# usb2serial.net
KiCad netlist of a schematic drawn in Altium Designer
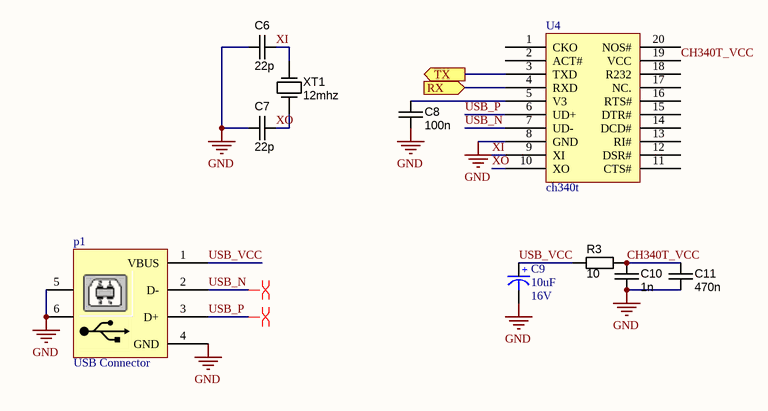
[diagram p0: usb2serial.SchDoc]

(export (version "E")
  (design (tool "Eeschema 10.0.6"))
  (components
    (comp (ref "C6")
      (value "22p")
      (footprint "CAPC1608X90N")
      (description "Capacitor 0603")
      (fields (field (name "TOLERANCE") "±10%"))
      (libsource (lib "PBL - Capacitors") (part "CAPC_1n_0603_X7R_100V_10%"))
    )
    (comp (ref "C7")
      (value "22p")
      (footprint "CAPC1608X90N")
      (description "Capacitor 0603")
      (fields (field (name "TOLERANCE") "±10%"))
      (libsource (lib "PBL - Capacitors") (part "CAPC_1n_0603_X7R_100V_10%"))
    )
    (comp (ref "C8")
      (value "100n")
      (footprint "CAPC1608X90N")
      (description "Capacitor 0603")
      (fields (field (name "TOLERANCE") "±10%"))
      (libsource (lib "PBL - Capacitors") (part "CAPC_1n_0603_X7R_100V_10%"))
    )
    (comp (ref "C9")
      (value "10uF")
      (footprint "cap 01")
      (description "Polar Capacitor")
      (fields (field (name "VOLTAGE") "16V") (field (name "DESIGNER") "Saeid Jorablo"))
      (libsource (lib "My Library") (part "Cap-Polar"))
    )
    (comp (ref "C10")
      (value "1n")
      (footprint "CAPC1608X90N")
      (description "Capacitor 0603")
      (fields (field (name "TOLERANCE") "±10%"))
      (libsource (lib "PBL - Capacitors") (part "CAPC_1n_0603_X7R_100V_10%"))
    )
    (comp (ref "C11")
      (value "470n")
      (footprint "CAPC1608X90N")
      (description "Capacitor 0603")
      (fields (field (name "TOLERANCE") "±10%"))
      (libsource (lib "PBL - Capacitors") (part "CAPC_1n_0603_X7R_100V_10%"))
    )
    (comp (ref "p1")
      (value "USB Connector")
      (footprint "USB2.5-2V4")
      (description "USB Connector-B Type")
      (fields (field (name "DESIGNER") "Eng. Saeid Jorablo"))
      (libsource (lib "My Library") (part "USB"))
    )
    (comp (ref "R3")
      (value "10")
      (footprint "RESC1608X55N")
      (description "Resistor 0603")
      (fields (field (name "TOLERANCE") "±5%"))
      (libsource (lib "PBL - Resistors") (part "RES_2K2_0603_5%"))
    )
    (comp (ref "U4")
      (value "ch340t")
      (footprint "LSSOP65P640X145-20N")
      (libsource (lib "sorour") (part "ch340t"))
    )
    (comp (ref "XT1")
      (value "12mhz")
      (footprint "CRYSTAL_HC49-US-SM")
      (description "Crystal")
      (libsource (lib "PBL - Resonators") (part "Crystal_6MHz_HC49/US"))
    )
  )
  (nets
    (net (code "1") (name "/CH340T_VCC") (class "Default")
      (node (ref "C10") (pin "2") (pintype "passive"))
      (node (ref "C11") (pin "2") (pintype "passive"))
      (node (ref "R3") (pin "2") (pinfunction "2_2") (pintype "passive"))
      (node (ref "U4") (pin "19") (pinfunction "VCC_19") (pintype "passive"))
    )
    (net (code "2") (name "/RX") (class "Default")
      (node (ref "U4") (pin "4") (pinfunction "RXD_4") (pintype "passive"))
    )
    (net (code "3") (name "/TX") (class "Default")
      (node (ref "U4") (pin "3") (pinfunction "TXD_3") (pintype "passive"))
    )
    (net (code "4") (name "/USB_N") (class "Default")
      (node (ref "U4") (pin "7") (pinfunction "UD-_7") (pintype "passive"))
      (node (ref "p1") (pin "2") (pinfunction "D-_2") (pintype "passive"))
    )
    (net (code "5") (name "/USB_P") (class "Default")
      (node (ref "U4") (pin "6") (pinfunction "UD+_6") (pintype "passive"))
      (node (ref "p1") (pin "3") (pinfunction "D+_3") (pintype "passive"))
    )
    (net (code "6") (name "/USB_VCC") (class "Default")
      (node (ref "C9") (pin "1") (pinfunction "+_1") (pintype "passive"))
      (node (ref "R3") (pin "1") (pinfunction "1_1") (pintype "passive"))
      (node (ref "p1") (pin "1") (pinfunction "VBUS_1") (pintype "power_in"))
    )
    (net (code "7") (name "/XI") (class "Default")
      (node (ref "C6") (pin "1") (pintype "passive"))
      (node (ref "U4") (pin "9") (pinfunction "XI_9") (pintype "passive"))
      (node (ref "XT1") (pin "2") (pinfunction "OUT_2") (pintype "passive"))
    )
    (net (code "8") (name "/XO") (class "Default")
      (node (ref "C7") (pin "1") (pintype "passive"))
      (node (ref "U4") (pin "10") (pinfunction "XO_10") (pintype "passive"))
      (node (ref "XT1") (pin "1") (pinfunction "IN_1") (pintype "passive"))
    )
    (net (code "9") (name "GND") (class "Default")
      (node (ref "C10") (pin "1") (pintype "passive"))
      (node (ref "C11") (pin "1") (pintype "passive"))
      (node (ref "C6") (pin "2") (pintype "passive"))
      (node (ref "C7") (pin "2") (pintype "passive"))
      (node (ref "C8") (pin "2") (pintype "passive"))
      (node (ref "C9") (pin "2") (pinfunction "-_2") (pintype "passive"))
      (node (ref "U4") (pin "8") (pinfunction "GND_8") (pintype "passive"))
      (node (ref "p1") (pin "4") (pinfunction "GND_4") (pintype "power_in"))
      (node (ref "p1") (pin "5") (pinfunction "5_5") (pintype "passive"))
      (node (ref "p1") (pin "6") (pinfunction "6_6") (pintype "passive"))
    )
    (net (code "10") (name "Net-(U4-V3)") (class "Default")
      (node (ref "C8") (pin "1") (pintype "passive"))
      (node (ref "U4") (pin "5") (pinfunction "V3_5") (pintype "passive"))
    )
    (net (code "11") (name "unconnected-(U4-ACT#-Pad2)") (class "Default")
      (node (ref "U4") (pin "2") (pinfunction "ACT#_2") (pintype "passive"))
    )
    (net (code "12") (name "unconnected-(U4-CKO-Pad1)") (class "Default")
      (node (ref "U4") (pin "1") (pinfunction "CKO_1") (pintype "passive"))
    )
    (net (code "13") (name "unconnected-(U4-CTS#-Pad11)") (class "Default")
      (node (ref "U4") (pin "11") (pinfunction "CTS#_11") (pintype "passive"))
    )
    (net (code "14") (name "unconnected-(U4-DCD#-Pad14)") (class "Default")
      (node (ref "U4") (pin "14") (pinfunction "DCD#_14") (pintype "passive"))
    )
    (net (code "15") (name "unconnected-(U4-DSR#-Pad12)") (class "Default")
      (node (ref "U4") (pin "12") (pinfunction "DSR#_12") (pintype "passive"))
    )
    (net (code "16") (name "unconnected-(U4-DTR#-Pad15)") (class "Default")
      (node (ref "U4") (pin "15") (pinfunction "DTR#_15") (pintype "passive"))
    )
    (net (code "17") (name "unconnected-(U4-NC.-Pad17)") (class "Default")
      (node (ref "U4") (pin "17") (pinfunction "NC._17") (pintype "passive"))
    )
    (net (code "18") (name "unconnected-(U4-NOS#-Pad20)") (class "Default")
      (node (ref "U4") (pin "20") (pinfunction "NOS#_20") (pintype "passive"))
    )
    (net (code "19") (name "unconnected-(U4-R232-Pad18)") (class "Default")
      (node (ref "U4") (pin "18") (pinfunction "R232_18") (pintype "passive"))
    )
    (net (code "20") (name "unconnected-(U4-RI#-Pad13)") (class "Default")
      (node (ref "U4") (pin "13") (pinfunction "RI#_13") (pintype "passive"))
    )
    (net (code "21") (name "unconnected-(U4-RTS#-Pad16)") (class "Default")
      (node (ref "U4") (pin "16") (pinfunction "RTS#_16") (pintype "passive"))
    )
  )
)
